# ATSAM3X8E_Main_Controller.net
KiCad netlist of a schematic drawn in Altium Designer
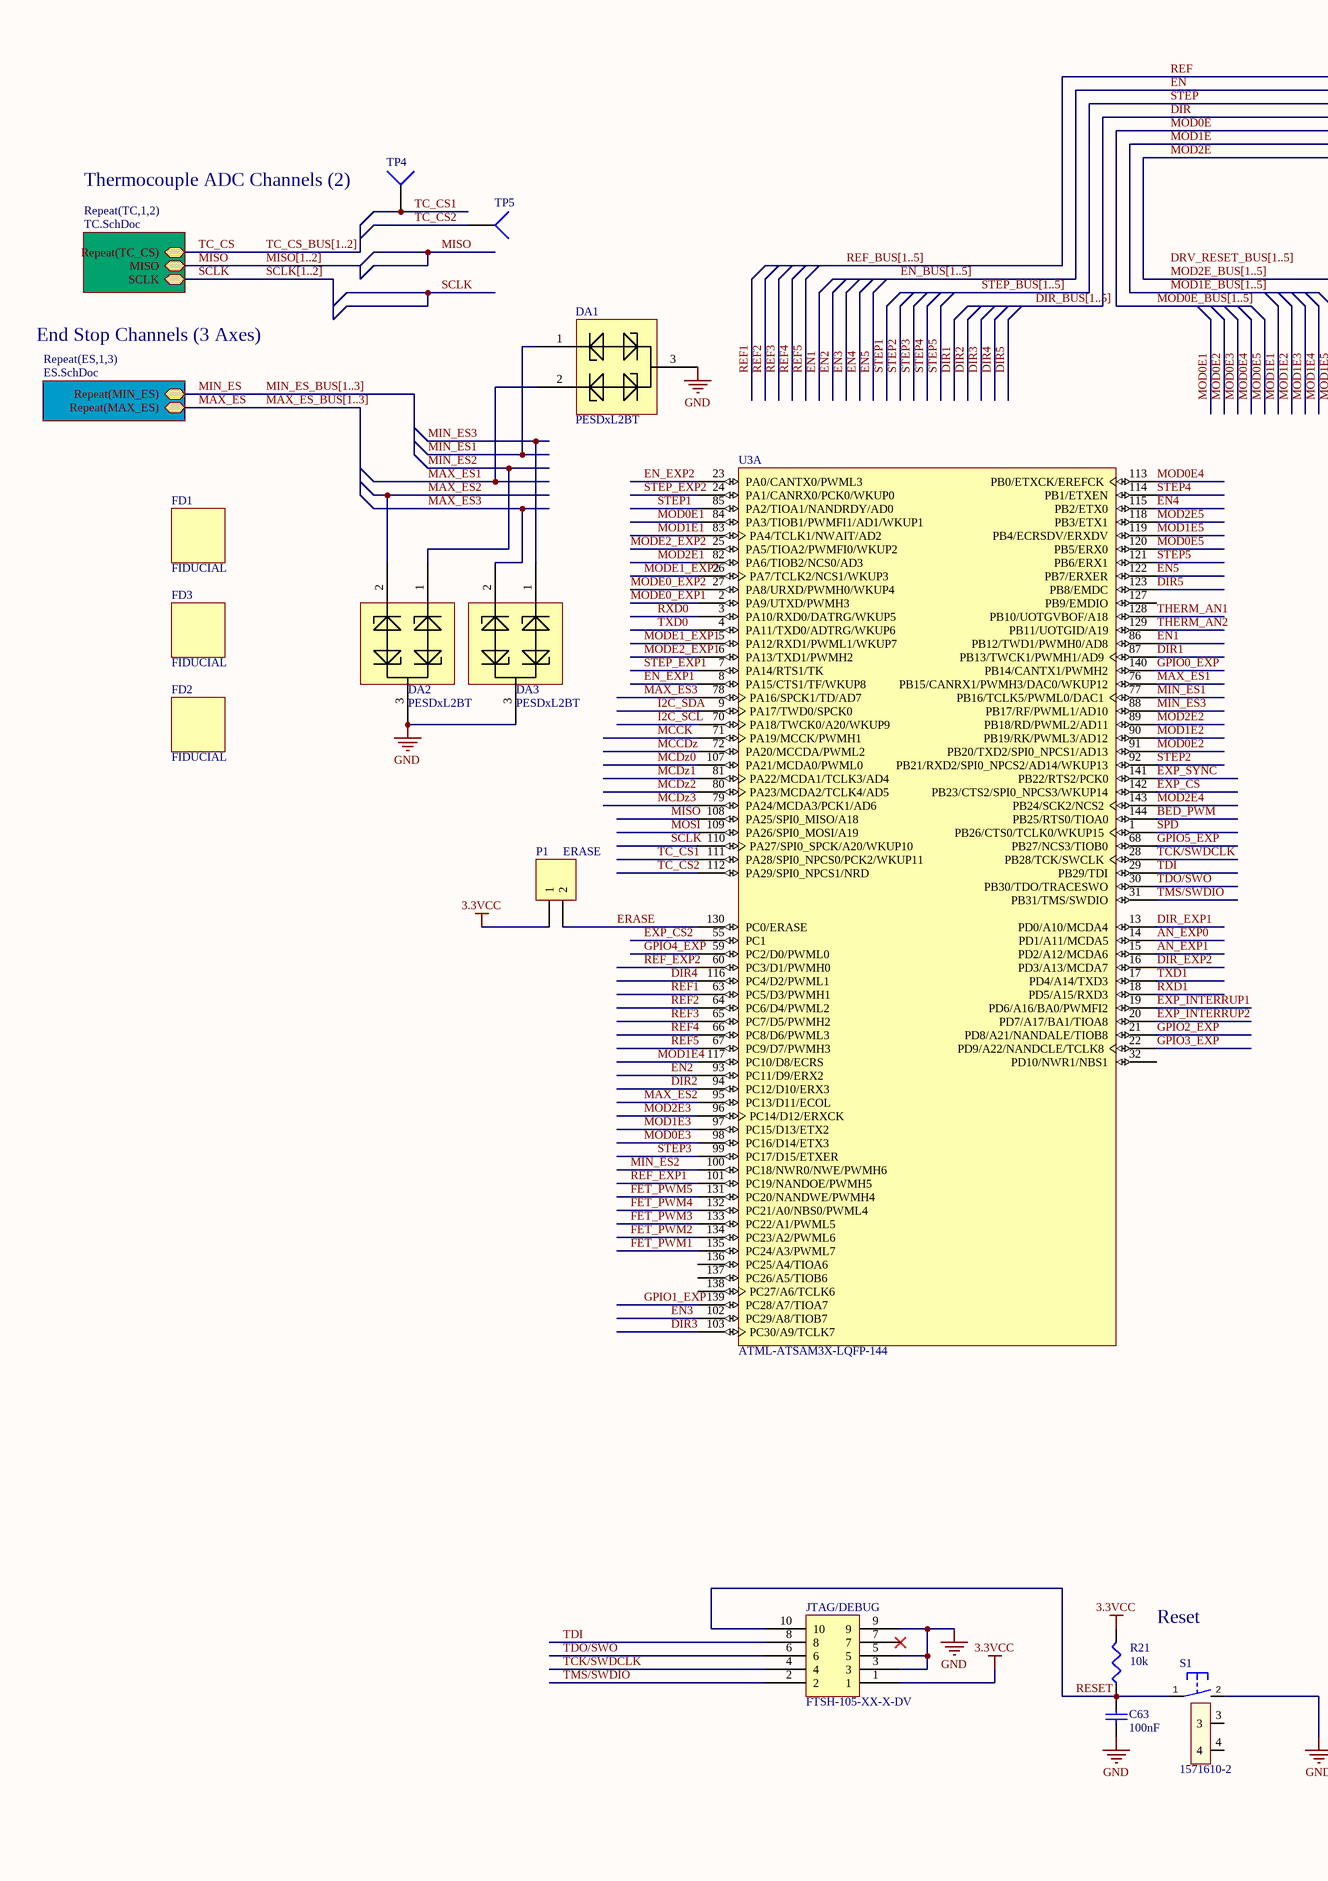
[diagram p0: ATSAM3X8E Main Controller.SchDoc, left]
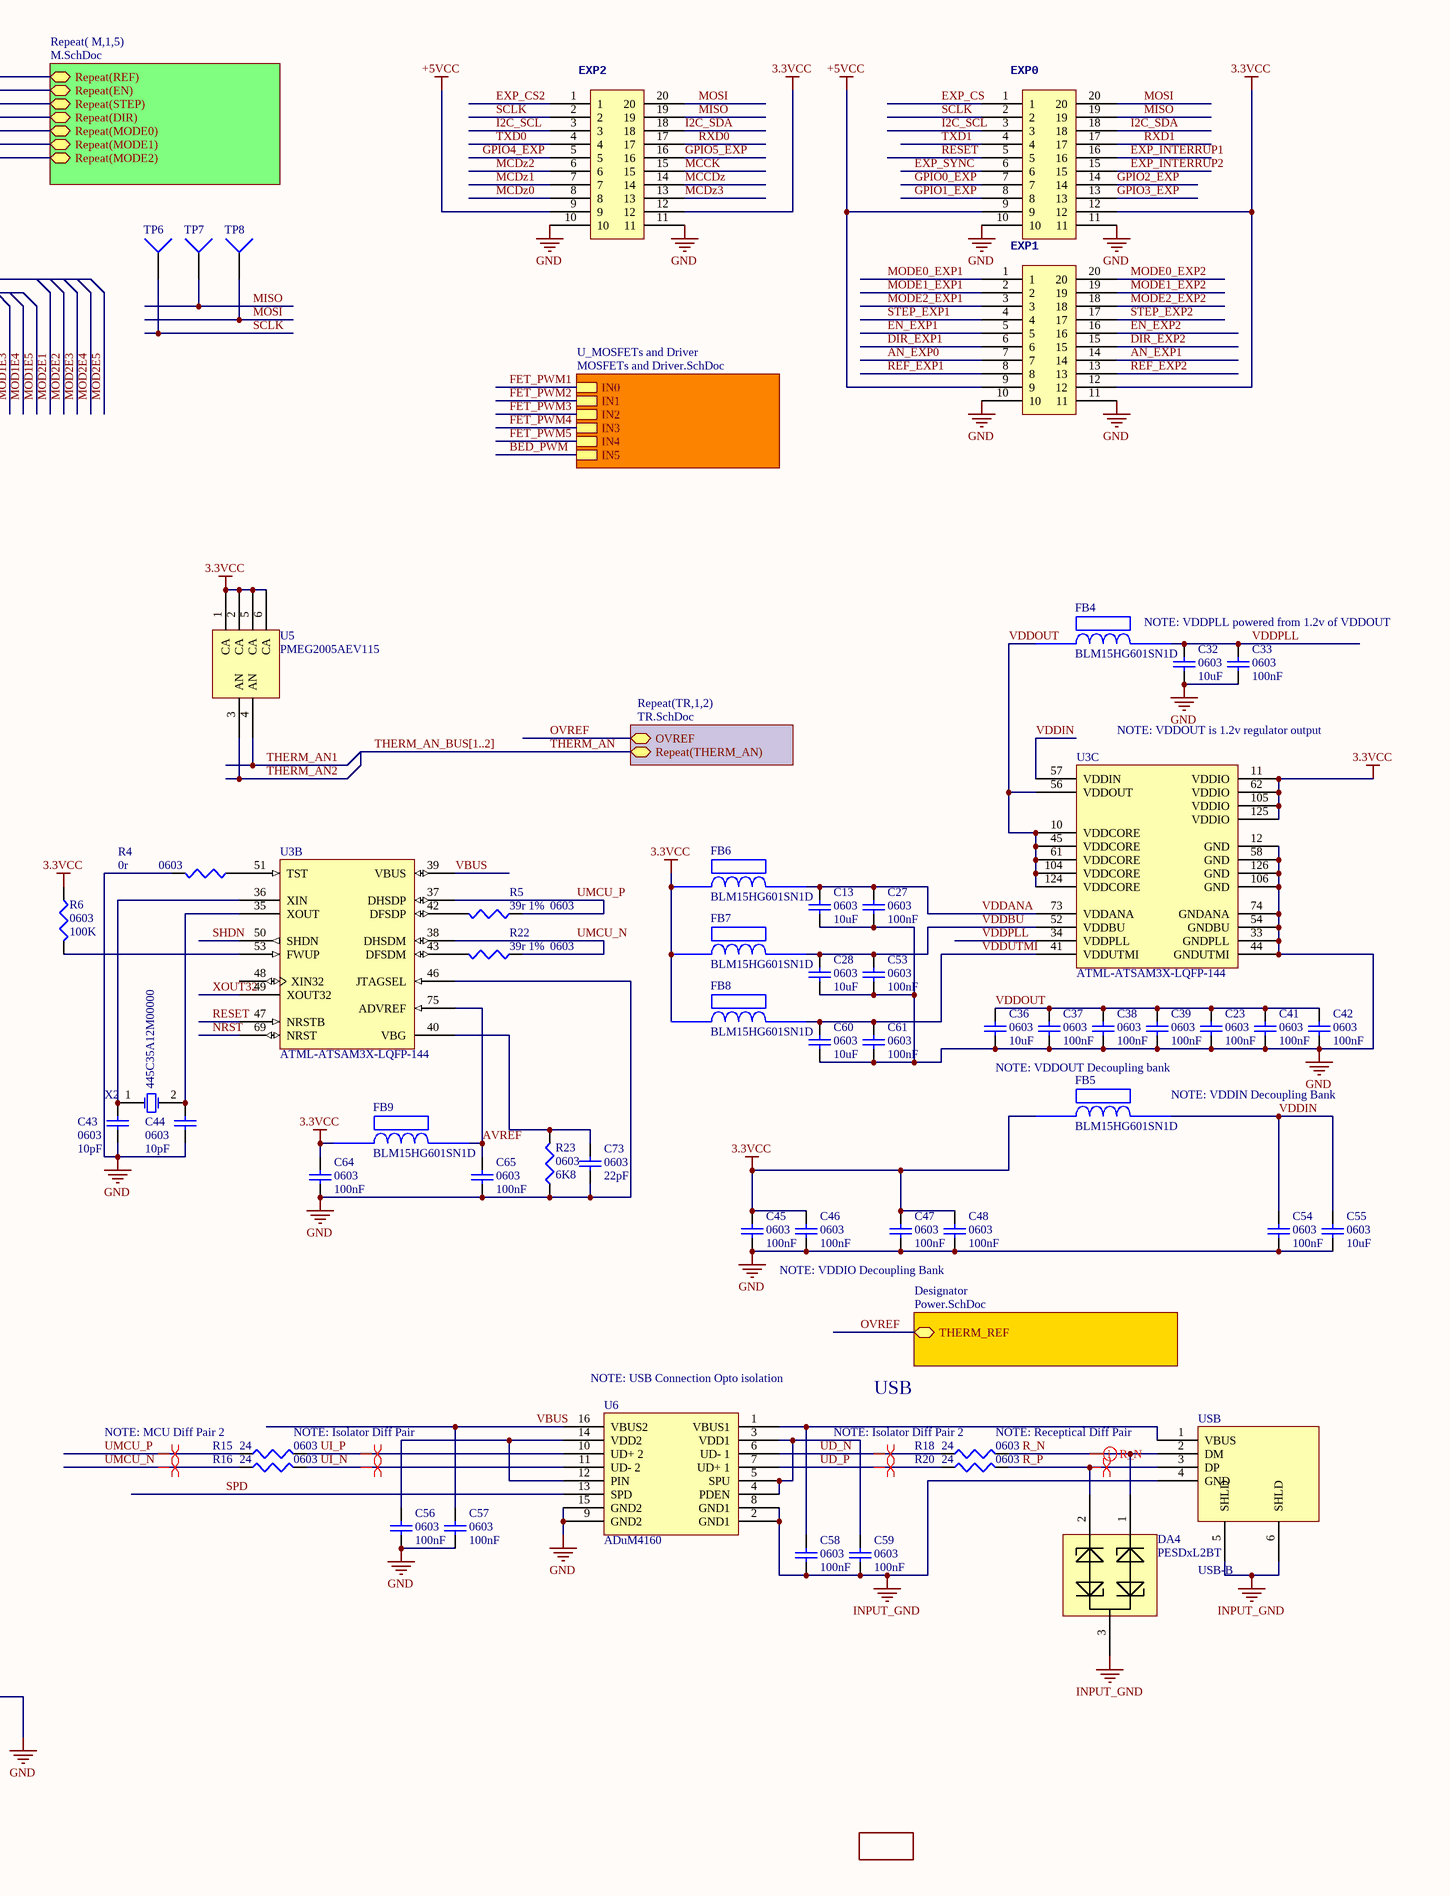
[diagram p1: ATSAM3X8E Main Controller.SchDoc, right]

(export (version "E")
  (design (tool "Eeschema 10.0.6"))
  (components
    (comp (ref "C13")
      (value "0603")
      (footprint "1608[0603]")
      (description "Capacitor (Semiconductor SIM Model)")
      (fields (field (name "ALTIUM_VALUE") "10uF") (field (name "PUBLISHER") "Altium Limited"))
      (libsource (lib "Miscellaneous Devices") (part "Cap Semi"))
    )
    (comp (ref "C23")
      (value "0603")
      (footprint "1608[0603]")
      (description "Capacitor (Semiconductor SIM Model)")
      (fields (field (name "ALTIUM_VALUE") "100nF") (field (name "PUBLISHER") "Altium Limited"))
      (libsource (lib "Miscellaneous Devices") (part "Cap Semi"))
    )
    (comp (ref "C27")
      (value "0603")
      (footprint "1608[0603]")
      (description "Capacitor (Semiconductor SIM Model)")
      (fields (field (name "ALTIUM_VALUE") "100nF") (field (name "PUBLISHER") "Altium Limited"))
      (libsource (lib "Miscellaneous Devices") (part "Cap Semi"))
    )
    (comp (ref "C28")
      (value "0603")
      (footprint "1608[0603]")
      (description "Capacitor (Semiconductor SIM Model)")
      (fields (field (name "ALTIUM_VALUE") "10uF") (field (name "PUBLISHER") "Altium Limited"))
      (libsource (lib "Miscellaneous Devices") (part "Cap Semi"))
    )
    (comp (ref "C32")
      (value "0603")
      (footprint "1608[0603]")
      (description "Capacitor (Semiconductor SIM Model)")
      (fields (field (name "ALTIUM_VALUE") "10uF") (field (name "PUBLISHER") "Altium Limited"))
      (libsource (lib "Miscellaneous Devices") (part "Cap Semi"))
    )
    (comp (ref "C33")
      (value "0603")
      (footprint "1608[0603]")
      (description "Capacitor (Semiconductor SIM Model)")
      (fields (field (name "ALTIUM_VALUE") "100nF") (field (name "PUBLISHER") "Altium Limited"))
      (libsource (lib "Miscellaneous Devices") (part "Cap Semi"))
    )
    (comp (ref "C36")
      (value "0603")
      (footprint "1608[0603]")
      (description "Capacitor (Semiconductor SIM Model)")
      (fields (field (name "ALTIUM_VALUE") "10uF") (field (name "PUBLISHER") "Altium Limited"))
      (libsource (lib "Miscellaneous Devices") (part "Cap Semi"))
    )
    (comp (ref "C37")
      (value "0603")
      (footprint "1608[0603]")
      (description "Capacitor (Semiconductor SIM Model)")
      (fields (field (name "ALTIUM_VALUE") "100nF") (field (name "PUBLISHER") "Altium Limited"))
      (libsource (lib "Miscellaneous Devices") (part "Cap Semi"))
    )
    (comp (ref "C38")
      (value "0603")
      (footprint "1608[0603]")
      (description "Capacitor (Semiconductor SIM Model)")
      (fields (field (name "ALTIUM_VALUE") "100nF") (field (name "PUBLISHER") "Altium Limited"))
      (libsource (lib "Miscellaneous Devices") (part "Cap Semi"))
    )
    (comp (ref "C39")
      (value "0603")
      (footprint "1608[0603]")
      (description "Capacitor (Semiconductor SIM Model)")
      (fields (field (name "ALTIUM_VALUE") "100nF") (field (name "PUBLISHER") "Altium Limited"))
      (libsource (lib "Miscellaneous Devices") (part "Cap Semi"))
    )
    (comp (ref "C41")
      (value "0603")
      (footprint "1608[0603]")
      (description "Capacitor (Semiconductor SIM Model)")
      (fields (field (name "ALTIUM_VALUE") "100nF") (field (name "PUBLISHER") "Altium Limited"))
      (libsource (lib "Miscellaneous Devices") (part "Cap Semi"))
    )
    (comp (ref "C42")
      (value "0603")
      (footprint "1608[0603]")
      (description "Capacitor (Semiconductor SIM Model)")
      (fields (field (name "ALTIUM_VALUE") "100nF") (field (name "PUBLISHER") "Altium Limited"))
      (libsource (lib "Miscellaneous Devices") (part "Cap Semi"))
    )
    (comp (ref "C43")
      (value "0603")
      (footprint "1608[0603]")
      (description "Capacitor (Semiconductor SIM Model)")
      (fields (field (name "ALTIUM_VALUE") "10pF") (field (name "PUBLISHER") "Altium Limited"))
      (libsource (lib "Miscellaneous Devices") (part "Cap Semi"))
    )
    (comp (ref "C44")
      (value "0603")
      (footprint "1608[0603]")
      (description "Capacitor (Semiconductor SIM Model)")
      (fields (field (name "ALTIUM_VALUE") "10pF") (field (name "PUBLISHER") "Altium Limited"))
      (libsource (lib "Miscellaneous Devices") (part "Cap Semi"))
    )
    (comp (ref "C45")
      (value "0603")
      (footprint "1608[0603]")
      (description "Capacitor (Semiconductor SIM Model)")
      (fields (field (name "ALTIUM_VALUE") "100nF") (field (name "PUBLISHER") "Altium Limited"))
      (libsource (lib "Miscellaneous Devices") (part "Cap Semi"))
    )
    (comp (ref "C46")
      (value "0603")
      (footprint "1608[0603]")
      (description "Capacitor (Semiconductor SIM Model)")
      (fields (field (name "ALTIUM_VALUE") "100nF") (field (name "PUBLISHER") "Altium Limited"))
      (libsource (lib "Miscellaneous Devices") (part "Cap Semi"))
    )
    (comp (ref "C47")
      (value "0603")
      (footprint "1608[0603]")
      (description "Capacitor (Semiconductor SIM Model)")
      (fields (field (name "ALTIUM_VALUE") "100nF") (field (name "PUBLISHER") "Altium Limited"))
      (libsource (lib "Miscellaneous Devices") (part "Cap Semi"))
    )
    (comp (ref "C48")
      (value "0603")
      (footprint "1608[0603]")
      (description "Capacitor (Semiconductor SIM Model)")
      (fields (field (name "ALTIUM_VALUE") "100nF") (field (name "PUBLISHER") "Altium Limited"))
      (libsource (lib "Miscellaneous Devices") (part "Cap Semi"))
    )
    (comp (ref "C53")
      (value "0603")
      (footprint "1608[0603]")
      (description "Capacitor (Semiconductor SIM Model)")
      (fields (field (name "ALTIUM_VALUE") "100nF") (field (name "PUBLISHER") "Altium Limited"))
      (libsource (lib "Miscellaneous Devices") (part "Cap Semi"))
    )
    (comp (ref "C54")
      (value "0603")
      (footprint "1608[0603]")
      (description "Capacitor (Semiconductor SIM Model)")
      (fields (field (name "ALTIUM_VALUE") "100nF") (field (name "PUBLISHER") "Altium Limited"))
      (libsource (lib "Miscellaneous Devices") (part "Cap Semi"))
    )
    (comp (ref "C55")
      (value "0603")
      (footprint "1608[0603]")
      (description "Capacitor (Semiconductor SIM Model)")
      (fields (field (name "ALTIUM_VALUE") "10uF") (field (name "PUBLISHER") "Altium Limited"))
      (libsource (lib "Miscellaneous Devices") (part "Cap Semi"))
    )
    (comp (ref "C56")
      (value "0603")
      (footprint "1608[0603]")
      (description "Capacitor (Semiconductor SIM Model)")
      (fields (field (name "ALTIUM_VALUE") "100nF") (field (name "PUBLISHER") "Altium Limited"))
      (libsource (lib "Miscellaneous Devices") (part "Cap Semi"))
    )
    (comp (ref "C57")
      (value "0603")
      (footprint "1608[0603]")
      (description "Capacitor (Semiconductor SIM Model)")
      (fields (field (name "ALTIUM_VALUE") "100nF") (field (name "PUBLISHER") "Altium Limited"))
      (libsource (lib "Miscellaneous Devices") (part "Cap Semi"))
    )
    (comp (ref "C58")
      (value "0603")
      (footprint "1608[0603]")
      (description "Capacitor (Semiconductor SIM Model)")
      (fields (field (name "ALTIUM_VALUE") "100nF") (field (name "PUBLISHER") "Altium Limited"))
      (libsource (lib "Miscellaneous Devices") (part "Cap Semi"))
    )
    (comp (ref "C59")
      (value "0603")
      (footprint "1608[0603]")
      (description "Capacitor (Semiconductor SIM Model)")
      (fields (field (name "ALTIUM_VALUE") "100nF") (field (name "PUBLISHER") "Altium Limited"))
      (libsource (lib "Miscellaneous Devices") (part "Cap Semi"))
    )
    (comp (ref "C60")
      (value "0603")
      (footprint "1608[0603]")
      (description "Capacitor (Semiconductor SIM Model)")
      (fields (field (name "ALTIUM_VALUE") "10uF") (field (name "PUBLISHER") "Altium Limited"))
      (libsource (lib "Miscellaneous Devices") (part "Cap Semi"))
    )
    (comp (ref "C61")
      (value "0603")
      (footprint "1608[0603]")
      (description "Capacitor (Semiconductor SIM Model)")
      (fields (field (name "ALTIUM_VALUE") "100nF") (field (name "PUBLISHER") "Altium Limited"))
      (libsource (lib "Miscellaneous Devices") (part "Cap Semi"))
    )
    (comp (ref "C63")
      (value "100nF")
      (footprint "1608[0603]")
      (description "Capacitor (Semiconductor SIM Model)")
      (fields (field (name "Comment") "Cap Semi") (field (name "PUBLISHER") "Altium Limited"))
      (libsource (lib "Miscellaneous Devices") (part "Cap Semi"))
    )
    (comp (ref "C64")
      (value "0603")
      (footprint "1608[0603]")
      (description "Capacitor (Semiconductor SIM Model)")
      (fields (field (name "ALTIUM_VALUE") "100nF") (field (name "PUBLISHER") "Altium Limited"))
      (libsource (lib "Miscellaneous Devices") (part "Cap Semi"))
    )
    (comp (ref "C65")
      (value "0603")
      (footprint "1608[0603]")
      (description "Capacitor (Semiconductor SIM Model)")
      (fields (field (name "ALTIUM_VALUE") "100nF") (field (name "PUBLISHER") "Altium Limited"))
      (libsource (lib "Miscellaneous Devices") (part "Cap Semi"))
    )
    (comp (ref "C73")
      (value "0603")
      (footprint "1608[0603]")
      (description "Capacitor (Semiconductor SIM Model)")
      (fields (field (name "ALTIUM_VALUE") "22pF") (field (name "PUBLISHER") "Altium Limited"))
      (libsource (lib "Miscellaneous Devices") (part "Cap Semi"))
    )
    (comp (ref "DA1")
      (value "PESDxL2BT")
      (footprint "SOT95P230X110-3N")
      (description "PESDxL2BT TVS Diode Array 2x")
      (libsource (lib "") (part "PESDxL2BT_1"))
    )
    (comp (ref "DA2")
      (value "PESDxL2BT")
      (footprint "SOT95P230X110-3N")
      (description "PESDxL2BT TVS Diode Array 2x")
      (libsource (lib "ZMBo Schematic Library") (part "PESDxL2BT"))
    )
    (comp (ref "DA3")
      (value "PESDxL2BT")
      (footprint "SOT95P230X110-3N")
      (description "PESDxL2BT TVS Diode Array 2x")
      (libsource (lib "ZMBo Schematic Library") (part "PESDxL2BT"))
    )
    (comp (ref "DA4")
      (value "PESDxL2BT")
      (footprint "SOT95P230X110-3N")
      (description "PESDxL2BT TVS Diode Array 2x")
      (libsource (lib "ZMBo Schematic Library") (part "PESDxL2BT"))
    )
    (comp (ref "EXP0")
      (value "10X2-0.1X0.05")
      (footprint "10X2-0.05X0.1w")
      (fields (field (name "PUBLISHER") "UltiMachine"))
      (libsource (lib "ZMBo Schematic Library") (part "10X2-0.1X0.05"))
    )
    (comp (ref "EXP1")
      (value "10X2-0.1X0.05")
      (footprint "10X2-0.05X0.1w")
      (fields (field (name "PUBLISHER") "UltiMachine"))
      (libsource (lib "ZMBo Schematic Library") (part "10X2-0.1X0.05"))
    )
    (comp (ref "EXP2")
      (value "10X2-0.1X0.05")
      (footprint "10X2-0.05X0.1w")
      (fields (field (name "PUBLISHER") "UltiMachine"))
      (libsource (lib "ZMBo Schematic Library") (part "10X2-0.1X0.05"))
    )
    (comp (ref "FB4")
      (value "BLM15HG601SN1D")
      (footprint "BLM18PG121SN1D")
      (libsource (lib "AHD Part Library") (part "BLM15HG601SN1D"))
    )
    (comp (ref "FB5")
      (value "BLM15HG601SN1D")
      (footprint "BLM18PG121SN1D")
      (libsource (lib "AHD Part Library") (part "BLM15HG601SN1D"))
    )
    (comp (ref "FB6")
      (value "BLM15HG601SN1D")
      (footprint "BLM18PG121SN1D")
      (libsource (lib "AHD Part Library") (part "BLM15HG601SN1D"))
    )
    (comp (ref "FB7")
      (value "BLM15HG601SN1D")
      (footprint "BLM18PG121SN1D")
      (libsource (lib "AHD Part Library") (part "BLM15HG601SN1D"))
    )
    (comp (ref "FB8")
      (value "BLM15HG601SN1D")
      (footprint "BLM18PG121SN1D")
      (libsource (lib "AHD Part Library") (part "BLM15HG601SN1D"))
    )
    (comp (ref "FB9")
      (value "BLM15HG601SN1D")
      (footprint "BLM18PG121SN1D")
      (libsource (lib "AHD Part Library") (part "BLM15HG601SN1D"))
    )
    (comp (ref "FD1")
      (value "FIDUCIAL")
      (footprint "FIDUCIAL-1X2")
      (libsource (lib "ZMBo Schematic Library") (part "FIDUCIAL"))
    )
    (comp (ref "FD2")
      (value "FIDUCIAL")
      (footprint "FIDUCIAL-1X2")
      (libsource (lib "ZMBo Schematic Library") (part "FIDUCIAL"))
    )
    (comp (ref "FD3")
      (value "FIDUCIAL")
      (footprint "FIDUCIAL-1X2")
      (libsource (lib "ZMBo Schematic Library") (part "FIDUCIAL"))
    )
    (comp (ref "JTAG/DEBUG")
      (value "FTSH-105-XX-X-DV")
      (footprint "FTSH-105-XX-X-DV")
      (libsource (lib "Adams Altium Library") (part "ARM Cortex JTAG-DEBUG Header"))
    )
    (comp (ref "LOGO1")
      (value "OSHW_LOGO_8MILX0150-NT")
      (footprint "OSHW_8X150_NOTEXT")
      (fields (field (name "PUBLISHER") "UltiMachine"))
      (libsource (lib "3Delight") (part "OSHW_LOGO_8MILX0150-NT"))
    )
    (comp (ref "P1")
      (value "ERASE")
      (footprint "HDR1X2")
      (description "Header, 2-Pin")
      (fields (field (name "PUBLISHER") "Altium Limited"))
      (libsource (lib "Miscellaneous Connectors") (part "Header 2"))
    )
    (comp (ref "R4")
      (value "0603")
      (footprint "J1-0603")
      (description "Resistor")
      (fields (field (name "ALTIUM_VALUE") "0r") (field (name "PUBLISHER") "Altium Limited"))
      (libsource (lib "Miscellaneous Devices") (part "Res3"))
    )
    (comp (ref "R5")
      (value "0603")
      (footprint "J1-0603")
      (description "Resistor")
      (fields (field (name "ALTIUM_VALUE") "39r 1%") (field (name "PUBLISHER") "Altium Limited"))
      (libsource (lib "Miscellaneous Devices") (part "Res3"))
    )
    (comp (ref "R6")
      (value "0603")
      (footprint "J1-0603")
      (description "Resistor")
      (fields (field (name "ALTIUM_VALUE") "100K") (field (name "PUBLISHER") "Altium Limited"))
      (libsource (lib "Miscellaneous Devices") (part "Res3"))
    )
    (comp (ref "R15")
      (value "0603")
      (footprint "J1-0603")
      (description "Resistor")
      (fields (field (name "ALTIUM_VALUE") "24") (field (name "PUBLISHER") "Altium Limited"))
      (libsource (lib "Miscellaneous Devices") (part "Res3"))
    )
    (comp (ref "R16")
      (value "0603")
      (footprint "J1-0603")
      (description "Resistor")
      (fields (field (name "ALTIUM_VALUE") "24") (field (name "PUBLISHER") "Altium Limited"))
      (libsource (lib "Miscellaneous Devices") (part "Res3"))
    )
    (comp (ref "R18")
      (value "0603")
      (footprint "J1-0603")
      (description "Resistor")
      (fields (field (name "ALTIUM_VALUE") "24") (field (name "PUBLISHER") "Altium Limited"))
      (libsource (lib "Miscellaneous Devices") (part "Res3"))
    )
    (comp (ref "R20")
      (value "0603")
      (footprint "J1-0603")
      (description "Resistor")
      (fields (field (name "ALTIUM_VALUE") "24") (field (name "PUBLISHER") "Altium Limited"))
      (libsource (lib "Miscellaneous Devices") (part "Res3"))
    )
    (comp (ref "R21")
      (value "10k")
      (footprint "J1-0603")
      (description "Resistor")
      (fields (field (name "Comment") "Res3") (field (name "PUBLISHER") "Altium Limited"))
      (libsource (lib "Miscellaneous Devices") (part "Res3"))
    )
    (comp (ref "R22")
      (value "0603")
      (footprint "J1-0603")
      (description "Resistor")
      (fields (field (name "ALTIUM_VALUE") "39r 1%") (field (name "PUBLISHER") "Altium Limited"))
      (libsource (lib "Miscellaneous Devices") (part "Res3"))
    )
    (comp (ref "R23")
      (value "0603")
      (footprint "J1-0603")
      (description "Resistor")
      (fields (field (name "ALTIUM_VALUE") "6K8") (field (name "PUBLISHER") "Altium Limited"))
      (libsource (lib "Miscellaneous Devices") (part "Res3"))
    )
    (comp (ref "S1")
      (value "1571610-2")
      (footprint "B3F-31XX")
      (description "SWTCH Momentary Washable")
      (fields
        (field (name "MANUFACTURER") "Omron")
        (field (name "MANUFACTURER_1") "TE")
        (field (name "PUBLISHER") "UltiMachine")
      )
      (libsource (lib "ZMBo Schematic Library") (part "1571610-2_1"))
    )
    (comp (ref "TP4")
      (value "TP4")
      (footprint "TP-2")
      (description "Socket")
      (fields (field (name "PUBLISHER") "Altium Limited"))
      (libsource (lib "ZMBo Schematic Library") (part "Socket"))
    )
    (comp (ref "TP5")
      (value "TP4")
      (footprint "TP-2")
      (description "Socket")
      (fields (field (name "PUBLISHER") "Altium Limited"))
      (libsource (lib "ZMBo Schematic Library") (part "Socket"))
    )
    (comp (ref "TP6")
      (value "TP4")
      (footprint "TP-2")
      (description "Socket")
      (fields (field (name "PUBLISHER") "Altium Limited"))
      (libsource (lib "ZMBo Schematic Library") (part "Socket"))
    )
    (comp (ref "TP7")
      (value "TP4")
      (footprint "TP-2")
      (description "Socket")
      (fields (field (name "PUBLISHER") "Altium Limited"))
      (libsource (lib "ZMBo Schematic Library") (part "Socket"))
    )
    (comp (ref "TP8")
      (value "TP4")
      (footprint "TP-2")
      (description "Socket")
      (fields (field (name "PUBLISHER") "Altium Limited"))
      (libsource (lib "ZMBo Schematic Library") (part "Socket"))
    )
    (comp (ref "U3")
      (value "ATML-ATSAM3X-LQFP-144")
      (footprint "LQFP144_N")
      (libsource (lib "ZMBo Schematic Library") (part "ATML-ATSAM3X-LQFP-144"))
    )
    (comp (ref "U5")
      (value "PMEG2005AEV115")
      (footprint "PMEG2005AEV115")
      (libsource (lib "Adams Altium Library") (part "PMEG2005AEV115"))
    )
    (comp (ref "U6")
      (value "ADuM4160")
      (footprint "ADuM4160")
      (description "USB Opto Isolator")
      (libsource (lib "ZMBo Schematic Library") (part "ADuM4160"))
    )
    (comp (ref "USB")
      (value "USB-B")
      (footprint "PN61729")
      (libsource (lib "ZMBo Schematic Library") (part "USB-B"))
    )
    (comp (ref "X2")
      (value "445C35A12M00000")
      (footprint "445C35A12M00000")
      (description "Crystal Oscillator")
      (fields (field (name "PUBLISHER") "Altium Limited"))
      (libsource (lib "Miscellaneous Devices") (part "XTAL"))
    )
  )
  (nets
    (net (code "55") (name "+5VCC") (class "Default")
      (node (ref "EXP0") (pin "9") (pinfunction "9_9") (pintype "passive"))
      (node (ref "EXP1") (pin "9") (pinfunction "9_9") (pintype "passive"))
      (node (ref "EXP2") (pin "9") (pinfunction "9_9") (pintype "passive"))
    )
    (net (code "56") (name "/AN_EXP0") (class "Default")
      (node (ref "EXP1") (pin "7") (pinfunction "7_7") (pintype "passive"))
      (node (ref "U3") (pin "14") (pinfunction "PD1/A11/MCDA5_14") (pintype "bidirectional"))
    )
    (net (code "57") (name "/AN_EXP1") (class "Default")
      (node (ref "EXP1") (pin "14") (pinfunction "14_14") (pintype "passive"))
      (node (ref "U3") (pin "15") (pinfunction "PD2/A12/MCDA6_15") (pintype "bidirectional"))
    )
    (net (code "58") (name "/AVREF") (class "Default")
      (node (ref "C65") (pin "2") (pinfunction "2_2") (pintype "passive"))
      (node (ref "FB9") (pin "2") (pinfunction "2_2") (pintype "passive"))
      (node (ref "U3") (pin "75") (pinfunction "ADVREF_75") (pintype "input"))
    )
    (net (code "59") (name "/BED_PWM") (class "Default")
      (node (ref "U3") (pin "144") (pinfunction "PB25/RTS0/TIOA0_144") (pintype "bidirectional"))
    )
    (net (code "61") (name "/DIR1") (class "Default")
      (node (ref "U3") (pin "87") (pinfunction "PB13/TWCK1/PWMH1/AD9_87") (pintype "bidirectional"))
    )
    (net (code "62") (name "/DIR2") (class "Default")
      (node (ref "U3") (pin "94") (pinfunction "PC12/D10/ERX3_94") (pintype "bidirectional"))
    )
    (net (code "63") (name "/DIR3") (class "Default")
      (node (ref "U3") (pin "103") (pinfunction "PC30/A9/TCLK7_103") (pintype "bidirectional"))
    )
    (net (code "64") (name "/DIR4") (class "Default")
      (node (ref "U3") (pin "116") (pinfunction "PC4/D2/PWML1_116") (pintype "bidirectional"))
    )
    (net (code "65") (name "/DIR5") (class "Default")
      (node (ref "U3") (pin "123") (pinfunction "PB8/EMDC_123") (pintype "bidirectional"))
    )
    (net (code "67") (name "/DIR_EXP1") (class "Default")
      (node (ref "EXP1") (pin "6") (pinfunction "6_6") (pintype "passive"))
      (node (ref "U3") (pin "13") (pinfunction "PD0/A10/MCDA4_13") (pintype "bidirectional"))
    )
    (net (code "68") (name "/DIR_EXP2") (class "Default")
      (node (ref "EXP1") (pin "15") (pinfunction "15_15") (pintype "passive"))
      (node (ref "U3") (pin "16") (pinfunction "PD3/A13/MCDA7_16") (pintype "bidirectional"))
    )
    (net (code "71") (name "/EN1") (class "Default")
      (node (ref "U3") (pin "86") (pinfunction "PB12/TWD1/PWMH0/AD8_86") (pintype "bidirectional"))
    )
    (net (code "72") (name "/EN2") (class "Default")
      (node (ref "U3") (pin "93") (pinfunction "PC11/D9/ERX2_93") (pintype "bidirectional"))
    )
    (net (code "73") (name "/EN3") (class "Default")
      (node (ref "U3") (pin "102") (pinfunction "PC29/A8/TIOB7_102") (pintype "bidirectional"))
    )
    (net (code "74") (name "/EN4") (class "Default")
      (node (ref "U3") (pin "115") (pinfunction "PB2/ETX0_115") (pintype "bidirectional"))
    )
    (net (code "75") (name "/EN5") (class "Default")
      (node (ref "U3") (pin "122") (pinfunction "PB7/ERXER_122") (pintype "bidirectional"))
    )
    (net (code "77") (name "/EN_EXP1") (class "Default")
      (node (ref "EXP1") (pin "5") (pinfunction "5_5") (pintype "passive"))
      (node (ref "U3") (pin "8") (pinfunction "PA15/CTS1/TF/WKUP8_8") (pintype "bidirectional"))
    )
    (net (code "78") (name "/EN_EXP2") (class "Default")
      (node (ref "EXP1") (pin "16") (pinfunction "16_16") (pintype "passive"))
      (node (ref "U3") (pin "23") (pinfunction "PA0/CANTX0/PWML3_23") (pintype "bidirectional"))
    )
    (net (code "79") (name "/ERASE") (class "Default")
      (node (ref "P1") (pin "2") (pinfunction "2_2") (pintype "passive"))
      (node (ref "U3") (pin "130") (pinfunction "PC0/ERASE_130") (pintype "bidirectional"))
    )
    (net (code "80") (name "/EXP_CS") (class "Default")
      (node (ref "EXP0") (pin "1") (pinfunction "1_1") (pintype "passive"))
      (node (ref "U3") (pin "142") (pinfunction "PB23/CTS2/SPI0_NPCS3/WKUP14_142") (pintype "bidirectional"))
    )
    (net (code "81") (name "/EXP_CS2") (class "Default")
      (node (ref "EXP2") (pin "1") (pinfunction "1_1") (pintype "passive"))
      (node (ref "U3") (pin "55") (pinfunction "PC1_55") (pintype "bidirectional"))
    )
    (net (code "82") (name "/EXP_INTERRUP1") (class "Default")
      (node (ref "EXP0") (pin "16") (pinfunction "16_16") (pintype "passive"))
      (node (ref "U3") (pin "19") (pinfunction "PD6/A16/BA0/PWMFI2_19") (pintype "bidirectional"))
    )
    (net (code "83") (name "/EXP_INTERRUP2") (class "Default")
      (node (ref "EXP0") (pin "15") (pinfunction "15_15") (pintype "passive"))
      (node (ref "U3") (pin "20") (pinfunction "PD7/A17/BA1/TIOA8_20") (pintype "bidirectional"))
    )
    (net (code "84") (name "/EXP_SYNC") (class "Default")
      (node (ref "EXP0") (pin "6") (pinfunction "6_6") (pintype "passive"))
      (node (ref "U3") (pin "141") (pinfunction "PB22/RTS2/PCK0_141") (pintype "bidirectional"))
    )
    (net (code "85") (name "/FET_PWM1") (class "Default")
      (node (ref "U3") (pin "135") (pinfunction "PC24/A3/PWML7_135") (pintype "bidirectional"))
    )
    (net (code "86") (name "/FET_PWM2") (class "Default")
      (node (ref "U3") (pin "134") (pinfunction "PC23/A2/PWML6_134") (pintype "bidirectional"))
    )
    (net (code "87") (name "/FET_PWM3") (class "Default")
      (node (ref "U3") (pin "133") (pinfunction "PC22/A1/PWML5_133") (pintype "bidirectional"))
    )
    (net (code "88") (name "/FET_PWM4") (class "Default")
      (node (ref "U3") (pin "132") (pinfunction "PC21/A0/NBS0/PWML4_132") (pintype "bidirectional"))
    )
    (net (code "89") (name "/FET_PWM5") (class "Default")
      (node (ref "U3") (pin "131") (pinfunction "PC20/NANDWE/PWMH4_131") (pintype "bidirectional"))
    )
    (net (code "90") (name "/GPIO0_EXP") (class "Default")
      (node (ref "EXP0") (pin "7") (pinfunction "7_7") (pintype "passive"))
      (node (ref "U3") (pin "140") (pinfunction "PB14/CANTX1/PWMH2_140") (pintype "bidirectional"))
    )
    (net (code "91") (name "/GPIO1_EXP") (class "Default")
      (node (ref "EXP0") (pin "8") (pinfunction "8_8") (pintype "passive"))
      (node (ref "U3") (pin "139") (pinfunction "PC28/A7/TIOA7_139") (pintype "bidirectional"))
    )
    (net (code "92") (name "/GPIO2_EXP") (class "Default")
      (node (ref "EXP0") (pin "14") (pinfunction "14_14") (pintype "passive"))
      (node (ref "U3") (pin "21") (pinfunction "PD8/A21/NANDALE/TIOB8_21") (pintype "bidirectional"))
    )
    (net (code "93") (name "/GPIO3_EXP") (class "Default")
      (node (ref "EXP0") (pin "13") (pinfunction "13_13") (pintype "passive"))
      (node (ref "U3") (pin "22") (pinfunction "PD9/A22/NANDCLE/TCLK8_22") (pintype "bidirectional"))
    )
    (net (code "94") (name "/GPIO4_EXP") (class "Default")
      (node (ref "EXP2") (pin "5") (pinfunction "5_5") (pintype "passive"))
      (node (ref "U3") (pin "59") (pinfunction "PC2/D0/PWML0_59") (pintype "bidirectional"))
    )
    (net (code "95") (name "/GPIO5_EXP") (class "Default")
      (node (ref "EXP2") (pin "16") (pinfunction "16_16") (pintype "passive"))
      (node (ref "U3") (pin "68") (pinfunction "PB27/NCS3/TIOB0_68") (pintype "bidirectional"))
    )
    (net (code "96") (name "/I2C_SCL") (class "Default")
      (node (ref "EXP0") (pin "3") (pinfunction "3_3") (pintype "passive"))
      (node (ref "EXP2") (pin "3") (pinfunction "3_3") (pintype "passive"))
      (node (ref "U3") (pin "70") (pinfunction "PA18/TWCK0/A20/WKUP9_70") (pintype "bidirectional"))
    )
    (net (code "97") (name "/I2C_SDA") (class "Default")
      (node (ref "EXP0") (pin "18") (pinfunction "18_18") (pintype "passive"))
      (node (ref "EXP2") (pin "18") (pinfunction "18_18") (pintype "passive"))
      (node (ref "U3") (pin "9") (pinfunction "PA17/TWD0/SPCK0_9") (pintype "bidirectional"))
    )
    (net (code "99") (name "/MAX_ES1") (class "Default")
      (node (ref "DA1") (pin "2") (pinfunction "2_2") (pintype "passive"))
      (node (ref "U3") (pin "76") (pinfunction "PB15/CANRX1/PWMH3/DAC0/WKUP12_76") (pintype "bidirectional"))
    )
    (net (code "100") (name "/MAX_ES2") (class "Default")
      (node (ref "DA2") (pin "2") (pinfunction "2_2") (pintype "passive"))
      (node (ref "U3") (pin "95") (pinfunction "PC13/D11/ECOL_95") (pintype "bidirectional"))
    )
    (net (code "101") (name "/MAX_ES3") (class "Default")
      (node (ref "DA3") (pin "2") (pinfunction "2_2") (pintype "passive"))
      (node (ref "U3") (pin "78") (pinfunction "PA16/SPCK1/TD/AD7_78") (pintype "bidirectional"))
    )
    (net (code "103") (name "/MCCDz") (class "Default")
      (node (ref "EXP2") (pin "14") (pinfunction "14_14") (pintype "passive"))
      (node (ref "U3") (pin "72") (pinfunction "PA20/MCCDA/PWML2_72") (pintype "bidirectional"))
    )
    (net (code "104") (name "/MCCK") (class "Default")
      (node (ref "EXP2") (pin "15") (pinfunction "15_15") (pintype "passive"))
      (node (ref "U3") (pin "71") (pinfunction "PA19/MCCK/PWMH1_71") (pintype "bidirectional"))
    )
    (net (code "105") (name "/MCDz0") (class "Default")
      (node (ref "EXP2") (pin "8") (pinfunction "8_8") (pintype "passive"))
      (node (ref "U3") (pin "107") (pinfunction "PA21/MCDA0/PWML0_107") (pintype "bidirectional"))
    )
    (net (code "106") (name "/MCDz1") (class "Default")
      (node (ref "EXP2") (pin "7") (pinfunction "7_7") (pintype "passive"))
      (node (ref "U3") (pin "81") (pinfunction "PA22/MCDA1/TCLK3/AD4_81") (pintype "bidirectional"))
    )
    (net (code "107") (name "/MCDz2") (class "Default")
      (node (ref "EXP2") (pin "6") (pinfunction "6_6") (pintype "passive"))
      (node (ref "U3") (pin "80") (pinfunction "PA23/MCDA2/TCLK4/AD5_80") (pintype "bidirectional"))
    )
    (net (code "108") (name "/MCDz3") (class "Default")
      (node (ref "EXP2") (pin "13") (pinfunction "13_13") (pintype "passive"))
      (node (ref "U3") (pin "79") (pinfunction "PA24/MCDA3/PCK1/AD6_79") (pintype "bidirectional"))
    )
    (net (code "110") (name "/MIN_ES1") (class "Default")
      (node (ref "DA1") (pin "1") (pinfunction "1_1") (pintype "passive"))
      (node (ref "U3") (pin "77") (pinfunction "PB16/TCLK5/PWML0/DAC1_77") (pintype "bidirectional"))
    )
    (net (code "111") (name "/MIN_ES2") (class "Default")
      (node (ref "DA2") (pin "1") (pinfunction "1_1") (pintype "passive"))
      (node (ref "U3") (pin "100") (pinfunction "PC18/NWR0/NWE/PWMH6_100") (pintype "bidirectional"))
    )
    (net (code "112") (name "/MIN_ES3") (class "Default")
      (node (ref "DA3") (pin "1") (pinfunction "1_1") (pintype "passive"))
      (node (ref "U3") (pin "88") (pinfunction "PB17/RF/PWML1/AD10_88") (pintype "bidirectional"))
    )
    (net (code "114") (name "/MISO") (class "Default")
      (node (ref "EXP0") (pin "19") (pinfunction "19_19") (pintype "passive"))
      (node (ref "EXP2") (pin "19") (pinfunction "19_19") (pintype "passive"))
      (node (ref "TP7") (pin "1") (pinfunction "1_1") (pintype "passive"))
      (node (ref "U3") (pin "108") (pinfunction "PA25/SPI0_MISO/A18_108") (pintype "bidirectional"))
    )
    (net (code "117") (name "/MOD0E1") (class "Default")
      (node (ref "U3") (pin "84") (pinfunction "PA3/TIOB1/PWMFI1/AD1/WKUP1_84") (pintype "bidirectional"))
    )
    (net (code "118") (name "/MOD0E2") (class "Default")
      (node (ref "U3") (pin "91") (pinfunction "PB20/TXD2/SPI0_NPCS1/AD13_91") (pintype "bidirectional"))
    )
    (net (code "119") (name "/MOD0E3") (class "Default")
      (node (ref "U3") (pin "98") (pinfunction "PC16/D14/ETX3_98") (pintype "bidirectional"))
    )
    (net (code "120") (name "/MOD0E4") (class "Default")
      (node (ref "U3") (pin "113") (pinfunction "PB0/ETXCK/EREFCK_113") (pintype "bidirectional"))
    )
    (net (code "121") (name "/MOD0E5") (class "Default")
      (node (ref "U3") (pin "120") (pinfunction "PB5/ERX0_120") (pintype "bidirectional"))
    )
    (net (code "124") (name "/MOD1E1") (class "Default")
      (node (ref "U3") (pin "83") (pinfunction "PA4/TCLK1/NWAIT/AD2_83") (pintype "bidirectional"))
    )
    (net (code "125") (name "/MOD1E2") (class "Default")
      (node (ref "U3") (pin "90") (pinfunction "PB19/RK/PWML3/AD12_90") (pintype "bidirectional"))
    )
    (net (code "126") (name "/MOD1E3") (class "Default")
      (node (ref "U3") (pin "97") (pinfunction "PC15/D13/ETX2_97") (pintype "bidirectional"))
    )
    (net (code "127") (name "/MOD1E4") (class "Default")
      (node (ref "U3") (pin "117") (pinfunction "PC10/D8/ECRS_117") (pintype "bidirectional"))
    )
    (net (code "128") (name "/MOD1E5") (class "Default")
      (node (ref "U3") (pin "119") (pinfunction "PB4/ECRSDV/ERXDV_119") (pintype "bidirectional"))
    )
    (net (code "131") (name "/MOD2E1") (class "Default")
      (node (ref "U3") (pin "82") (pinfunction "PA6/TIOB2/NCS0/AD3_82") (pintype "bidirectional"))
    )
    (net (code "132") (name "/MOD2E2") (class "Default")
      (node (ref "U3") (pin "89") (pinfunction "PB18/RD/PWML2/AD11_89") (pintype "bidirectional"))
    )
    (net (code "133") (name "/MOD2E3") (class "Default")
      (node (ref "U3") (pin "96") (pinfunction "PC14/D12/ERXCK_96") (pintype "bidirectional"))
    )
    (net (code "134") (name "/MOD2E4") (class "Default")
      (node (ref "U3") (pin "143") (pinfunction "PB24/SCK2/NCS2_143") (pintype "bidirectional"))
    )
    (net (code "135") (name "/MOD2E5") (class "Default")
      (node (ref "U3") (pin "118") (pinfunction "PB3/ETX1_118") (pintype "bidirectional"))
    )
    (net (code "137") (name "/MODE0_EXP1") (class "Default")
      (node (ref "EXP1") (pin "1") (pinfunction "1_1") (pintype "passive"))
      (node (ref "U3") (pin "2") (pinfunction "PA9/UTXD/PWMH3_2") (pintype "bidirectional"))
    )
    (net (code "138") (name "/MODE0_EXP2") (class "Default")
      (node (ref "EXP1") (pin "20") (pinfunction "20_20") (pintype "passive"))
      (node (ref "U3") (pin "27") (pinfunction "PA8/URXD/PWMH0/WKUP4_27") (pintype "bidirectional"))
    )
    (net (code "139") (name "/MODE1_EXP1") (class "Default")
      (node (ref "EXP1") (pin "2") (pinfunction "2_2") (pintype "passive"))
      (node (ref "U3") (pin "5") (pinfunction "PA12/RXD1/PWML1/WKUP7_5") (pintype "bidirectional"))
    )
    (net (code "140") (name "/MODE1_EXP2") (class "Default")
      (node (ref "EXP1") (pin "19") (pinfunction "19_19") (pintype "passive"))
      (node (ref "U3") (pin "26") (pinfunction "PA7/TCLK2/NCS1/WKUP3_26") (pintype "bidirectional"))
    )
    (net (code "141") (name "/MODE2_EXP1") (class "Default")
      (node (ref "EXP1") (pin "3") (pinfunction "3_3") (pintype "passive"))
      (node (ref "U3") (pin "6") (pinfunction "PA13/TXD1/PWMH2_6") (pintype "bidirectional"))
    )
    (net (code "142") (name "/MODE2_EXP2") (class "Default")
      (node (ref "EXP1") (pin "18") (pinfunction "18_18") (pintype "passive"))
      (node (ref "U3") (pin "25") (pinfunction "PA5/TIOA2/PWMFI0/WKUP2_25") (pintype "bidirectional"))
    )
    (net (code "143") (name "/MOSI") (class "Default")
      (node (ref "EXP0") (pin "20") (pinfunction "20_20") (pintype "passive"))
      (node (ref "EXP2") (pin "20") (pinfunction "20_20") (pintype "passive"))
      (node (ref "TP8") (pin "1") (pinfunction "1_1") (pintype "passive"))
      (node (ref "U3") (pin "109") (pinfunction "PA26/SPI0_MOSI/A19_109") (pintype "bidirectional"))
    )
    (net (code "144") (name "/NRST") (class "Default")
      (node (ref "U3") (pin "69") (pinfunction "NRST_69") (pintype "bidirectional"))
    )
    (net (code "147") (name "/REF1") (class "Default")
      (node (ref "U3") (pin "63") (pinfunction "PC5/D3/PWMH1_63") (pintype "bidirectional"))
    )
    (net (code "148") (name "/REF2") (class "Default")
      (node (ref "U3") (pin "64") (pinfunction "PC6/D4/PWML2_64") (pintype "bidirectional"))
    )
    (net (code "149") (name "/REF3") (class "Default")
      (node (ref "U3") (pin "65") (pinfunction "PC7/D5/PWMH2_65") (pintype "bidirectional"))
    )
    (net (code "150") (name "/REF4") (class "Default")
      (node (ref "U3") (pin "66") (pinfunction "PC8/D6/PWML3_66") (pintype "bidirectional"))
    )
    (net (code "151") (name "/REF5") (class "Default")
      (node (ref "U3") (pin "67") (pinfunction "PC9/D7/PWMH3_67") (pintype "bidirectional"))
    )
    (net (code "153") (name "/REF_EXP1") (class "Default")
      (node (ref "EXP1") (pin "8") (pinfunction "8_8") (pintype "passive"))
      (node (ref "U3") (pin "101") (pinfunction "PC19/NANDOE/PWMH5_101") (pintype "bidirectional"))
    )
    (net (code "154") (name "/REF_EXP2") (class "Default")
      (node (ref "EXP1") (pin "13") (pinfunction "13_13") (pintype "passive"))
      (node (ref "U3") (pin "60") (pinfunction "PC3/D1/PWMH0_60") (pintype "bidirectional"))
    )
    (net (code "155") (name "/RESET") (class "Default")
      (node (ref "C63") (pin "2") (pinfunction "2_2") (pintype "passive"))
      (node (ref "EXP0") (pin "5") (pinfunction "5_5") (pintype "passive"))
      (node (ref "JTAG/DEBUG") (pin "10") (pinfunction "10_10") (pintype "passive"))
      (node (ref "R21") (pin "1") (pinfunction "1_1") (pintype "passive"))
      (node (ref "S1") (pin "1") (pinfunction "P_1") (pintype "passive"))
      (node (ref "U3") (pin "47") (pinfunction "NRSTB_47") (pintype "input"))
    )
    (net (code "156") (name "/RXD0") (class "Default")
      (node (ref "EXP2") (pin "17") (pinfunction "17_17") (pintype "passive"))
      (node (ref "U3") (pin "3") (pinfunction "PA10/RXD0/DATRG/WKUP5_3") (pintype "bidirectional"))
    )
    (net (code "157") (name "/RXD1") (class "Default")
      (node (ref "EXP0") (pin "17") (pinfunction "17_17") (pintype "passive"))
      (node (ref "U3") (pin "18") (pinfunction "PD5/A15/RXD3_18") (pintype "bidirectional"))
    )
    (net (code "158") (name "/R_N") (class "Default")
      (node (ref "DA4") (pin "1") (pinfunction "1_1") (pintype "passive"))
      (node (ref "R18") (pin "2") (pinfunction "2_2") (pintype "passive"))
      (node (ref "USB") (pin "2") (pinfunction "DM_2") (pintype "passive"))
    )
    (net (code "159") (name "/R_P") (class "Default")
      (node (ref "DA4") (pin "2") (pinfunction "2_2") (pintype "passive"))
      (node (ref "R20") (pin "2") (pinfunction "2_2") (pintype "passive"))
      (node (ref "USB") (pin "3") (pinfunction "DP_3") (pintype "passive"))
    )
    (net (code "160") (name "/SCLK") (class "Default")
      (node (ref "EXP0") (pin "2") (pinfunction "2_2") (pintype "passive"))
      (node (ref "EXP2") (pin "2") (pinfunction "2_2") (pintype "passive"))
      (node (ref "TP6") (pin "1") (pinfunction "1_1") (pintype "passive"))
      (node (ref "U3") (pin "110") (pinfunction "PA27/SPI0_SPCK/A20/WKUP10_110") (pintype "bidirectional"))
    )
    (net (code "162") (name "/SHDN") (class "Default")
      (node (ref "U3") (pin "50") (pinfunction "SHDN_50") (pintype "output"))
    )
    (net (code "163") (name "/SPD") (class "Default")
      (node (ref "U3") (pin "1") (pinfunction "PB26/CTS0/TCLK0/WKUP15_1") (pintype "bidirectional"))
      (node (ref "U6") (pin "13") (pinfunction "SPD_13") (pintype "passive"))
    )
    (net (code "165") (name "/STEP1") (class "Default")
      (node (ref "U3") (pin "85") (pinfunction "PA2/TIOA1/NANDRDY/AD0_85") (pintype "bidirectional"))
    )
    (net (code "166") (name "/STEP2") (class "Default")
      (node (ref "U3") (pin "92") (pinfunction "PB21/RXD2/SPI0_NPCS2/AD14/WKUP13_92") (pintype "bidirectional"))
    )
    (net (code "167") (name "/STEP3") (class "Default")
      (node (ref "U3") (pin "99") (pinfunction "PC17/D15/ETXER_99") (pintype "bidirectional"))
    )
    (net (code "168") (name "/STEP4") (class "Default")
      (node (ref "U3") (pin "114") (pinfunction "PB1/ETXEN_114") (pintype "bidirectional"))
    )
    (net (code "169") (name "/STEP5") (class "Default")
      (node (ref "U3") (pin "121") (pinfunction "PB6/ERX1_121") (pintype "bidirectional"))
    )
    (net (code "171") (name "/STEP_EXP1") (class "Default")
      (node (ref "EXP1") (pin "4") (pinfunction "4_4") (pintype "passive"))
      (node (ref "U3") (pin "7") (pinfunction "PA14/RTS1/TK_7") (pintype "bidirectional"))
    )
    (net (code "172") (name "/STEP_EXP2") (class "Default")
      (node (ref "EXP1") (pin "17") (pinfunction "17_17") (pintype "passive"))
      (node (ref "U3") (pin "24") (pinfunction "PA1/CANRX0/PCK0/WKUP0_24") (pintype "bidirectional"))
    )
    (net (code "173") (name "/TCK{slash}SWDCLK") (class "Default")
      (node (ref "JTAG/DEBUG") (pin "4") (pinfunction "4_4") (pintype "passive"))
      (node (ref "U3") (pin "28") (pinfunction "PB28/TCK/SWCLK_28") (pintype "bidirectional"))
    )
    (net (code "175") (name "/TC_CS1") (class "Default")
      (node (ref "TP4") (pin "1") (pinfunction "1_1") (pintype "passive"))
      (node (ref "U3") (pin "111") (pinfunction "PA28/SPI0_NPCS0/PCK2/WKUP11_111") (pintype "bidirectional"))
    )
    (net (code "176") (name "/TC_CS2") (class "Default")
      (node (ref "TP5") (pin "1") (pinfunction "1_1") (pintype "passive"))
      (node (ref "U3") (pin "112") (pinfunction "PA29/SPI0_NPCS1/NRD_112") (pintype "bidirectional"))
    )
    (net (code "178") (name "/TDI") (class "Default")
      (node (ref "JTAG/DEBUG") (pin "8") (pinfunction "8_8") (pintype "passive"))
      (node (ref "U3") (pin "29") (pinfunction "PB29/TDI_29") (pintype "bidirectional"))
    )
    (net (code "179") (name "/TDO{slash}SWO") (class "Default")
      (node (ref "JTAG/DEBUG") (pin "6") (pinfunction "6_6") (pintype "passive"))
      (node (ref "U3") (pin "30") (pinfunction "PB30/TDO/TRACESWO_30") (pintype "bidirectional"))
    )
    (net (code "181") (name "/THERM_AN1") (class "Default")
      (node (ref "U3") (pin "128") (pinfunction "PB10/UOTGVBOF/A18_128") (pintype "bidirectional"))
      (node (ref "U5") (pin "4") (pinfunction "AN_4") (pintype "passive"))
    )
    (net (code "182") (name "/THERM_AN2") (class "Default")
      (node (ref "U3") (pin "129") (pinfunction "PB11/UOTGID/A19_129") (pintype "bidirectional"))
      (node (ref "U5") (pin "3") (pinfunction "AN_3") (pintype "passive"))
    )
    (net (code "184") (name "/TMS{slash}SWDIO") (class "Default")
      (node (ref "JTAG/DEBUG") (pin "2") (pinfunction "2_2") (pintype "passive"))
      (node (ref "U3") (pin "31") (pinfunction "PB31/TMS/SWDIO_31") (pintype "bidirectional"))
    )
    (net (code "185") (name "/TXD0") (class "Default")
      (node (ref "EXP2") (pin "4") (pinfunction "4_4") (pintype "passive"))
      (node (ref "U3") (pin "4") (pinfunction "PA11/TXD0/ADTRG/WKUP6_4") (pintype "bidirectional"))
    )
    (net (code "186") (name "/TXD1") (class "Default")
      (node (ref "EXP0") (pin "4") (pinfunction "4_4") (pintype "passive"))
      (node (ref "U3") (pin "17") (pinfunction "PD4/A14/TXD3_17") (pintype "bidirectional"))
    )
    (net (code "187") (name "/UD_N") (class "Default")
      (node (ref "R18") (pin "1") (pinfunction "1_1") (pintype "passive"))
      (node (ref "U6") (pin "6") (pinfunction "UD-_1_6") (pintype "passive"))
    )
    (net (code "188") (name "/UD_P") (class "Default")
      (node (ref "R20") (pin "1") (pinfunction "1_1") (pintype "passive"))
      (node (ref "U6") (pin "7") (pinfunction "UD+_1_7") (pintype "passive"))
    )
    (net (code "189") (name "/UI_N") (class "Default")
      (node (ref "R16") (pin "2") (pinfunction "2_2") (pintype "passive"))
      (node (ref "U6") (pin "11") (pinfunction "UD-_2_11") (pintype "passive"))
    )
    (net (code "190") (name "/UI_P") (class "Default")
      (node (ref "R15") (pin "2") (pinfunction "2_2") (pintype "passive"))
      (node (ref "U6") (pin "10") (pinfunction "UD+_2_10") (pintype "passive"))
    )
    (net (code "191") (name "/UMCU_N") (class "Default")
      (node (ref "R16") (pin "1") (pinfunction "1_1") (pintype "passive"))
      (node (ref "R22") (pin "1") (pinfunction "1_1") (pintype "passive"))
      (node (ref "U3") (pin "38") (pinfunction "DHSDM_38") (pintype "bidirectional"))
    )
    (net (code "192") (name "/UMCU_P") (class "Default")
      (node (ref "R15") (pin "1") (pinfunction "1_1") (pintype "passive"))
      (node (ref "R5") (pin "1") (pinfunction "1_1") (pintype "passive"))
      (node (ref "U3") (pin "37") (pinfunction "DHSDP_37") (pintype "bidirectional"))
    )
    (net (code "193") (name "/VBUS") (class "Default")
      (node (ref "C57") (pin "2") (pinfunction "2_2") (pintype "passive"))
      (node (ref "U3") (pin "39") (pinfunction "VBUS_39") (pintype "bidirectional"))
      (node (ref "U6") (pin "16") (pinfunction "VBUS2_16") (pintype "passive"))
    )
    (net (code "194") (name "/VDDANA") (class "Default")
      (node (ref "C13") (pin "2") (pinfunction "2_2") (pintype "passive"))
      (node (ref "C27") (pin "2") (pinfunction "2_2") (pintype "passive"))
      (node (ref "FB6") (pin "2") (pinfunction "2_2") (pintype "passive"))
      (node (ref "U3") (pin "73") (pinfunction "VDDANA_73") (pintype "power_in"))
    )
    (net (code "195") (name "/VDDBU") (class "Default")
      (node (ref "C28") (pin "2") (pinfunction "2_2") (pintype "passive"))
      (node (ref "C53") (pin "2") (pinfunction "2_2") (pintype "passive"))
      (node (ref "FB7") (pin "2") (pinfunction "2_2") (pintype "passive"))
      (node (ref "U3") (pin "52") (pinfunction "VDDBU_52") (pintype "power_in"))
    )
    (net (code "196") (name "/VDDIN") (class "Default")
      (node (ref "C54") (pin "2") (pinfunction "2_2") (pintype "passive"))
      (node (ref "C55") (pin "2") (pinfunction "2_2") (pintype "passive"))
      (node (ref "FB5") (pin "2") (pinfunction "2_2") (pintype "passive"))
      (node (ref "U3") (pin "57") (pinfunction "VDDIN_57") (pintype "power_in"))
    )
    (net (code "197") (name "/VDDOUT") (class "Default")
      (node (ref "C23") (pin "2") (pinfunction "2_2") (pintype "passive"))
      (node (ref "C36") (pin "2") (pinfunction "2_2") (pintype "passive"))
      (node (ref "C37") (pin "2") (pinfunction "2_2") (pintype "passive"))
      (node (ref "C38") (pin "2") (pinfunction "2_2") (pintype "passive"))
      (node (ref "C39") (pin "2") (pinfunction "2_2") (pintype "passive"))
      (node (ref "C41") (pin "2") (pinfunction "2_2") (pintype "passive"))
      (node (ref "C42") (pin "2") (pinfunction "2_2") (pintype "passive"))
      (node (ref "FB4") (pin "1") (pinfunction "1_1") (pintype "passive"))
      (node (ref "U3") (pin "10") (pinfunction "VDDCORE_10") (pintype "power_in"))
      (node (ref "U3") (pin "104") (pinfunction "VDDCORE_104") (pintype "power_in"))
      (node (ref "U3") (pin "124") (pinfunction "VDDCORE_124") (pintype "power_in"))
      (node (ref "U3") (pin "45") (pinfunction "VDDCORE_45") (pintype "power_in"))
      (node (ref "U3") (pin "56") (pinfunction "VDDOUT_56") (pintype "power_in"))
      (node (ref "U3") (pin "61") (pinfunction "VDDCORE_61") (pintype "power_in"))
    )
    (net (code "198") (name "/VDDPLL") (class "Default")
      (node (ref "C32") (pin "2") (pinfunction "2_2") (pintype "passive"))
      (node (ref "C33") (pin "2") (pinfunction "2_2") (pintype "passive"))
      (node (ref "FB4") (pin "2") (pinfunction "2_2") (pintype "passive"))
      (node (ref "U3") (pin "34") (pinfunction "VDDPLL_34") (pintype "power_in"))
    )
    (net (code "199") (name "/VDDUTMI") (class "Default")
      (node (ref "C60") (pin "2") (pinfunction "2_2") (pintype "passive"))
      (node (ref "C61") (pin "2") (pinfunction "2_2") (pintype "passive"))
      (node (ref "FB8") (pin "2") (pinfunction "2_2") (pintype "passive"))
      (node (ref "U3") (pin "41") (pinfunction "VDDUTMI_41") (pintype "power_in"))
    )
    (net (code "200") (name "/XOUT32") (class "Default")
      (node (ref "U3") (pin "49") (pinfunction "XOUT32_49") (pintype "passive"))
    )
    (net (code "201") (name "3.3VCC") (class "Default")
      (node (ref "C45") (pin "2") (pinfunction "2_2") (pintype "passive"))
      (node (ref "C46") (pin "2") (pinfunction "2_2") (pintype "passive"))
      (node (ref "C47") (pin "2") (pinfunction "2_2") (pintype "passive"))
      (node (ref "C48") (pin "2") (pinfunction "2_2") (pintype "passive"))
      (node (ref "C64") (pin "2") (pinfunction "2_2") (pintype "passive"))
      (node (ref "EXP0") (pin "12") (pinfunction "12_12") (pintype "passive"))
      (node (ref "EXP1") (pin "12") (pinfunction "12_12") (pintype "passive"))
      (node (ref "EXP2") (pin "12") (pinfunction "12_12") (pintype "passive"))
      (node (ref "FB5") (pin "1") (pinfunction "1_1") (pintype "passive"))
      (node (ref "FB6") (pin "1") (pinfunction "1_1") (pintype "passive"))
      (node (ref "FB7") (pin "1") (pinfunction "1_1") (pintype "passive"))
      (node (ref "FB8") (pin "1") (pinfunction "1_1") (pintype "passive"))
      (node (ref "FB9") (pin "1") (pinfunction "1_1") (pintype "passive"))
      (node (ref "JTAG/DEBUG") (pin "1") (pinfunction "1_1") (pintype "passive"))
      (node (ref "P1") (pin "1") (pinfunction "1_1") (pintype "passive"))
      (node (ref "R21") (pin "2") (pinfunction "2_2") (pintype "passive"))
      (node (ref "R6") (pin "1") (pinfunction "1_1") (pintype "passive"))
      (node (ref "U3") (pin "105") (pinfunction "VDDIO_105") (pintype "power_in"))
      (node (ref "U3") (pin "11") (pinfunction "VDDIO_11") (pintype "power_in"))
      (node (ref "U3") (pin "125") (pinfunction "VDDIO_125") (pintype "power_in"))
      (node (ref "U3") (pin "62") (pinfunction "VDDIO_62") (pintype "power_in"))
      (node (ref "U5") (pin "1") (pinfunction "CA_1") (pintype "passive"))
      (node (ref "U5") (pin "2") (pinfunction "CA_2") (pintype "passive"))
      (node (ref "U5") (pin "5") (pinfunction "CA_5") (pintype "passive"))
      (node (ref "U5") (pin "6") (pinfunction "CA_6") (pintype "passive"))
    )
    (net (code "202") (name "GND") (class "Default")
      (node (ref "C13") (pin "1") (pinfunction "1_1") (pintype "passive"))
      (node (ref "C23") (pin "1") (pinfunction "1_1") (pintype "passive"))
      (node (ref "C27") (pin "1") (pinfunction "1_1") (pintype "passive"))
      (node (ref "C28") (pin "1") (pinfunction "1_1") (pintype "passive"))
      (node (ref "C32") (pin "1") (pinfunction "1_1") (pintype "passive"))
      (node (ref "C33") (pin "1") (pinfunction "1_1") (pintype "passive"))
      (node (ref "C36") (pin "1") (pinfunction "1_1") (pintype "passive"))
      (node (ref "C37") (pin "1") (pinfunction "1_1") (pintype "passive"))
      (node (ref "C38") (pin "1") (pinfunction "1_1") (pintype "passive"))
      (node (ref "C39") (pin "1") (pinfunction "1_1") (pintype "passive"))
      (node (ref "C41") (pin "1") (pinfunction "1_1") (pintype "passive"))
      (node (ref "C42") (pin "1") (pinfunction "1_1") (pintype "passive"))
      (node (ref "C43") (pin "1") (pinfunction "1_1") (pintype "passive"))
      (node (ref "C44") (pin "1") (pinfunction "1_1") (pintype "passive"))
      (node (ref "C45") (pin "1") (pinfunction "1_1") (pintype "passive"))
      (node (ref "C46") (pin "1") (pinfunction "1_1") (pintype "passive"))
      (node (ref "C47") (pin "1") (pinfunction "1_1") (pintype "passive"))
      (node (ref "C48") (pin "1") (pinfunction "1_1") (pintype "passive"))
      (node (ref "C53") (pin "1") (pinfunction "1_1") (pintype "passive"))
      (node (ref "C54") (pin "1") (pinfunction "1_1") (pintype "passive"))
      (node (ref "C55") (pin "1") (pinfunction "1_1") (pintype "passive"))
      (node (ref "C56") (pin "1") (pinfunction "1_1") (pintype "passive"))
      (node (ref "C57") (pin "1") (pinfunction "1_1") (pintype "passive"))
      (node (ref "C60") (pin "1") (pinfunction "1_1") (pintype "passive"))
      (node (ref "C61") (pin "1") (pinfunction "1_1") (pintype "passive"))
      (node (ref "C63") (pin "1") (pinfunction "1_1") (pintype "passive"))
      (node (ref "C64") (pin "1") (pinfunction "1_1") (pintype "passive"))
      (node (ref "C65") (pin "1") (pinfunction "1_1") (pintype "passive"))
      (node (ref "C73") (pin "1") (pinfunction "1_1") (pintype "passive"))
      (node (ref "DA1") (pin "3") (pinfunction "3_3") (pintype "passive"))
      (node (ref "DA2") (pin "3") (pinfunction "3_3") (pintype "passive"))
      (node (ref "DA3") (pin "3") (pinfunction "3_3") (pintype "passive"))
      (node (ref "EXP0") (pin "10") (pinfunction "10_10") (pintype "passive"))
      (node (ref "EXP0") (pin "11") (pinfunction "11_11") (pintype "passive"))
      (node (ref "EXP1") (pin "10") (pinfunction "10_10") (pintype "passive"))
      (node (ref "EXP1") (pin "11") (pinfunction "11_11") (pintype "passive"))
      (node (ref "EXP2") (pin "10") (pinfunction "10_10") (pintype "passive"))
      (node (ref "EXP2") (pin "11") (pinfunction "11_11") (pintype "passive"))
      (node (ref "JTAG/DEBUG") (pin "3") (pinfunction "3_3") (pintype "passive"))
      (node (ref "JTAG/DEBUG") (pin "5") (pinfunction "5_5") (pintype "passive"))
      (node (ref "JTAG/DEBUG") (pin "9") (pinfunction "9_9") (pintype "passive"))
      (node (ref "R23") (pin "1") (pinfunction "1_1") (pintype "passive"))
      (node (ref "R4") (pin "2") (pinfunction "2_2") (pintype "passive"))
      (node (ref "S1") (pin "2") (pinfunction "S_2") (pintype "passive"))
      (node (ref "U3") (pin "106") (pinfunction "GND_106") (pintype "power_in"))
      (node (ref "U3") (pin "12") (pinfunction "GND_12") (pintype "power_in"))
      (node (ref "U3") (pin "126") (pinfunction "GND_126") (pintype "power_in"))
      (node (ref "U3") (pin "33") (pinfunction "GNDPLL_33") (pintype "power_in"))
      (node (ref "U3") (pin "44") (pinfunction "GNDUTMI_44") (pintype "power_in"))
      (node (ref "U3") (pin "46") (pinfunction "JTAGSEL_46") (pintype "input"))
      (node (ref "U3") (pin "54") (pinfunction "GNDBU_54") (pintype "power_in"))
      (node (ref "U3") (pin "58") (pinfunction "GND_58") (pintype "power_in"))
      (node (ref "U3") (pin "74") (pinfunction "GNDANA_74") (pintype "power_in"))
      (node (ref "U6") (pin "15") (pinfunction "GND2_15") (pintype "passive"))
      (node (ref "U6") (pin "9") (pinfunction "GND2_9") (pintype "passive"))
    )
    (net (code "203") (name "INPUT_GND") (class "Default")
      (node (ref "C58") (pin "1") (pinfunction "1_1") (pintype "passive"))
      (node (ref "C59") (pin "1") (pinfunction "1_1") (pintype "passive"))
      (node (ref "DA4") (pin "3") (pinfunction "3_3") (pintype "passive"))
      (node (ref "U6") (pin "2") (pinfunction "GND1_2") (pintype "passive"))
      (node (ref "U6") (pin "8") (pinfunction "GND1_8") (pintype "passive"))
      (node (ref "USB") (pin "4") (pinfunction "GND_4") (pintype "passive"))
      (node (ref "USB") (pin "5") (pinfunction "SHLD_5") (pintype "passive"))
      (node (ref "USB") (pin "6") (pinfunction "SHLD_6") (pintype "passive"))
    )
    (net (code "204") (name "Net-(U3B-DFSDM)") (class "Default")
      (node (ref "R22") (pin "2") (pinfunction "2_2") (pintype "passive"))
      (node (ref "U3") (pin "43") (pinfunction "DFSDM_43") (pintype "bidirectional"))
    )
    (net (code "205") (name "Net-(U3B-DFSDP)") (class "Default")
      (node (ref "R5") (pin "2") (pinfunction "2_2") (pintype "passive"))
      (node (ref "U3") (pin "42") (pinfunction "DFSDP_42") (pintype "bidirectional"))
    )
    (net (code "206") (name "Net-(U3B-FWUP)") (class "Default")
      (node (ref "R6") (pin "2") (pinfunction "2_2") (pintype "passive"))
      (node (ref "U3") (pin "53") (pinfunction "FWUP_53") (pintype "input"))
    )
    (net (code "207") (name "Net-(U3B-TST)") (class "Default")
      (node (ref "R4") (pin "1") (pinfunction "1_1") (pintype "passive"))
      (node (ref "U3") (pin "51") (pinfunction "TST_51") (pintype "input"))
    )
    (net (code "208") (name "Net-(U3B-VBG)") (class "Default")
      (node (ref "C73") (pin "2") (pinfunction "2_2") (pintype "passive"))
      (node (ref "R23") (pin "2") (pinfunction "2_2") (pintype "passive"))
      (node (ref "U3") (pin "40") (pinfunction "VBG_40") (pintype "passive"))
    )
    (net (code "209") (name "Net-(U3B-XIN)") (class "Default")
      (node (ref "C43") (pin "2") (pinfunction "2_2") (pintype "passive"))
      (node (ref "U3") (pin "36") (pinfunction "XIN_36") (pintype "passive"))
      (node (ref "X2") (pin "1") (pinfunction "OSC1_1") (pintype "passive"))
    )
    (net (code "210") (name "Net-(U3B-XOUT)") (class "Default")
      (node (ref "C44") (pin "2") (pinfunction "2_2") (pintype "passive"))
      (node (ref "U3") (pin "35") (pinfunction "XOUT_35") (pintype "passive"))
      (node (ref "X2") (pin "2") (pinfunction "OSC2_2") (pintype "passive"))
    )
    (net (code "211") (name "Net-(U6-PDEN)") (class "Default")
      (node (ref "C59") (pin "2") (pinfunction "2_2") (pintype "passive"))
      (node (ref "U6") (pin "3") (pinfunction "VDD1_3") (pintype "passive"))
      (node (ref "U6") (pin "4") (pinfunction "PDEN_4") (pintype "passive"))
      (node (ref "U6") (pin "5") (pinfunction "SPU_5") (pintype "passive"))
    )
    (net (code "212") (name "Net-(U6-PIN)") (class "Default")
      (node (ref "C56") (pin "2") (pinfunction "2_2") (pintype "passive"))
      (node (ref "U6") (pin "12") (pinfunction "PIN_12") (pintype "passive"))
      (node (ref "U6") (pin "14") (pinfunction "VDD2_14") (pintype "passive"))
    )
    (net (code "213") (name "Net-(U6-VBUS1)") (class "Default")
      (node (ref "C58") (pin "2") (pinfunction "2_2") (pintype "passive"))
      (node (ref "U6") (pin "1") (pinfunction "VBUS1_1") (pintype "passive"))
      (node (ref "USB") (pin "1") (pinfunction "VBUS_1") (pintype "passive"))
    )
    (net (code "214") (name "unconnected-(JTAG/DEBUG-Pad7)") (class "Default")
      (node (ref "JTAG/DEBUG") (pin "7") (pinfunction "7_7") (pintype "passive+no_connect"))
    )
    (net (code "215") (name "unconnected-(S1-Pad3)") (class "Default")
      (node (ref "S1") (pin "3") (pinfunction "3_3") (pintype "power_in"))
    )
    (net (code "216") (name "unconnected-(S1-Pad4)") (class "Default")
      (node (ref "S1") (pin "4") (pinfunction "4_4") (pintype "power_in"))
    )
    (net (code "217") (name "unconnected-(U3A-PB9{slash}EMDIO-Pad127)") (class "Default")
      (node (ref "U3") (pin "127") (pinfunction "PB9/EMDIO_127") (pintype "bidirectional"))
    )
    (net (code "218") (name "unconnected-(U3A-PC25{slash}A4{slash}TIOA6-Pad136)") (class "Default")
      (node (ref "U3") (pin "136") (pinfunction "PC25/A4/TIOA6_136") (pintype "bidirectional"))
    )
    (net (code "219") (name "unconnected-(U3A-PC26{slash}A5{slash}TIOB6-Pad137)") (class "Default")
      (node (ref "U3") (pin "137") (pinfunction "PC26/A5/TIOB6_137") (pintype "bidirectional"))
    )
    (net (code "220") (name "unconnected-(U3A-PC27{slash}A6{slash}TCLK6-Pad138)") (class "Default")
      (node (ref "U3") (pin "138") (pinfunction "PC27/A6/TCLK6_138") (pintype "bidirectional"))
    )
    (net (code "221") (name "unconnected-(U3A-PD10{slash}NWR1{slash}NBS1-Pad32)") (class "Default")
      (node (ref "U3") (pin "32") (pinfunction "PD10/NWR1/NBS1_32") (pintype "bidirectional"))
    )
    (net (code "222") (name "unconnected-(U3B-XIN32-Pad48)") (class "Default")
      (node (ref "U3") (pin "48") (pinfunction "XIN32_48") (pintype "bidirectional"))
    )
  )
)
